# LEDs.net
KiCad netlist of a schematic drawn in Altium Designer
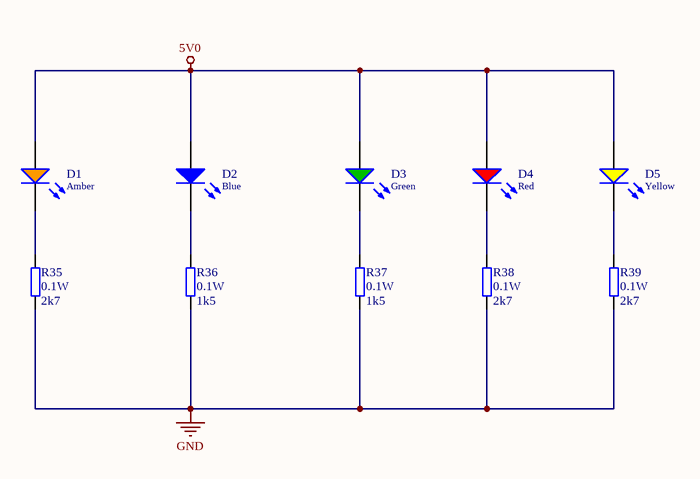
[diagram p0: LEDs.SchDoc]

(export (version "E")
  (design (tool "Eeschema 10.0.6"))
  (components
    (comp (ref "D1")
      (value "Amber")
      (footprint "WL-SMCW_0603")
      (description "WL-SMCW SMD Mono-color Chip LED Waterclear, size 0603, Red, 2 V, 140°")
      (fields (field (name "EMITTING COLOR") "Amber") (field (name "CREATED") "2020-01-07_Thilo_Wendt"))
      (libsource (lib "optoelectronics") (part "LED_Amber"))
    )
    (comp (ref "D2")
      (value "Blue")
      (footprint "WL-SMCW_0603")
      (description "WL-SMCW SMD Mono-color Chip LED Waterclear, size 0603, Blue, 3.2 V, 140°")
      (fields
        (field (name "MPN") "150060BS75000")
        (field (name "MF") "Wuerth Elektronik")
        (field (name "EMITTING COLOR") "Blue")
        (field (name "CREATED") "2018_09_06_AGeiger")
      )
      (libsource (lib "optoelectronics") (part "LED_Blue"))
    )
    (comp (ref "D3")
      (value "Green")
      (footprint "WL-SMCW_0603")
      (description "WL-SMCW SMD Mono-color Chip LED Waterclear, size 0603, Green, 3.2 V, 140°")
      (fields
        (field (name "MPN") "150060GS75000")
        (field (name "MF") "Wuerth Elektronik")
        (field (name "EMITTING COLOR") "Green")
        (field (name "CREATED") "2018_09_06_AGeiger")
      )
      (libsource (lib "optoelectronics") (part "LED_Green"))
    )
    (comp (ref "D4")
      (value "Red")
      (footprint "WL-SMCW_0603")
      (description "WL-SMCW SMD Mono-color Chip LED Waterclear, size 0603, Red, 2 V, 140°")
      (fields
        (field (name "MPN") "150060RS75000")
        (field (name "MF") "Wuerth Elektronik")
        (field (name "EMITTING COLOR") "Red")
        (field (name "CREATED") "2018_09_06_AGeiger")
      )
      (libsource (lib "optoelectronics") (part "LED_Red"))
    )
    (comp (ref "D5")
      (value "Yellow")
      (footprint "WL-SMCW_0603")
      (description "WL-SMCW SMD Mono-color Chip LED Waterclear, size 0603, Red, 2 V, 140°")
      (fields (field (name "EMITTING COLOR") "Yellow") (field (name "CREATED") "2020-01-07_Thilo_Wendt"))
      (libsource (lib "optoelectronics") (part "LED_Yellow"))
    )
    (comp (ref "R35")
      (value "0.1W")
      (footprint "RESC1608X55X30NL15T15")
      (description "Standard thick film resistor")
      (fields (field (name "ALTIUM_VALUE") "2k7") (field (name "CREATED") "2019-12-08_Thilo_Wendt"))
      (libsource (lib "standard_rlc") (part "R_0.1W_SMD"))
    )
    (comp (ref "R36")
      (value "0.1W")
      (footprint "RESC1608X55X30NL15T15")
      (description "Standard thick film resistor")
      (fields (field (name "ALTIUM_VALUE") "1k5") (field (name "CREATED") "2019-12-08_Thilo_Wendt"))
      (libsource (lib "standard_rlc") (part "R_0.1W_SMD"))
    )
    (comp (ref "R37")
      (value "0.1W")
      (footprint "RESC1608X55X30NL15T15")
      (description "Standard thick film resistor")
      (fields (field (name "ALTIUM_VALUE") "1k5") (field (name "CREATED") "2019-12-08_Thilo_Wendt"))
      (libsource (lib "standard_rlc") (part "R_0.1W_SMD"))
    )
    (comp (ref "R38")
      (value "0.1W")
      (footprint "RESC1608X55X30NL15T15")
      (description "Standard thick film resistor")
      (fields (field (name "ALTIUM_VALUE") "2k7") (field (name "CREATED") "2019-12-08_Thilo_Wendt"))
      (libsource (lib "standard_rlc") (part "R_0.1W_SMD"))
    )
    (comp (ref "R39")
      (value "0.1W")
      (footprint "RESC1608X55X30NL15T15")
      (description "Standard thick film resistor")
      (fields (field (name "ALTIUM_VALUE") "2k7") (field (name "CREATED") "2019-12-08_Thilo_Wendt"))
      (libsource (lib "standard_rlc") (part "R_0.1W_SMD"))
    )
  )
  (nets
    (net (code "1") (name "5V0") (class "Default")
      (node (ref "D1") (pin "2") (pinfunction "A_2") (pintype "passive"))
      (node (ref "D2") (pin "2") (pinfunction "A_2") (pintype "passive"))
      (node (ref "D3") (pin "2") (pinfunction "A_2") (pintype "passive"))
      (node (ref "D4") (pin "2") (pinfunction "A_2") (pintype "passive"))
      (node (ref "D5") (pin "2") (pinfunction "A_2") (pintype "passive"))
    )
    (net (code "2") (name "GND") (class "Default")
      (node (ref "R35") (pin "2") (pinfunction "2_2") (pintype "passive"))
      (node (ref "R36") (pin "2") (pinfunction "2_2") (pintype "passive"))
      (node (ref "R37") (pin "2") (pinfunction "2_2") (pintype "passive"))
      (node (ref "R38") (pin "2") (pinfunction "2_2") (pintype "passive"))
      (node (ref "R39") (pin "2") (pinfunction "2_2") (pintype "passive"))
    )
    (net (code "3") (name "Net-(D1-K)") (class "Default")
      (node (ref "D1") (pin "1") (pinfunction "K_1") (pintype "passive"))
      (node (ref "R35") (pin "1") (pinfunction "1_1") (pintype "passive"))
    )
    (net (code "4") (name "Net-(D2-K)") (class "Default")
      (node (ref "D2") (pin "1") (pinfunction "K_1") (pintype "passive"))
      (node (ref "R36") (pin "1") (pinfunction "1_1") (pintype "passive"))
    )
    (net (code "5") (name "Net-(D3-K)") (class "Default")
      (node (ref "D3") (pin "1") (pinfunction "K_1") (pintype "passive"))
      (node (ref "R37") (pin "1") (pinfunction "1_1") (pintype "passive"))
    )
    (net (code "6") (name "Net-(D4-K)") (class "Default")
      (node (ref "D4") (pin "1") (pinfunction "K_1") (pintype "passive"))
      (node (ref "R38") (pin "1") (pinfunction "1_1") (pintype "passive"))
    )
    (net (code "7") (name "Net-(D5-K)") (class "Default")
      (node (ref "D5") (pin "1") (pinfunction "K_1") (pintype "passive"))
      (node (ref "R39") (pin "1") (pinfunction "1_1") (pintype "passive"))
    )
  )
)
